# Bartosz_Nowakowski.net
KiCad netlist of a schematic drawn in EAGLE
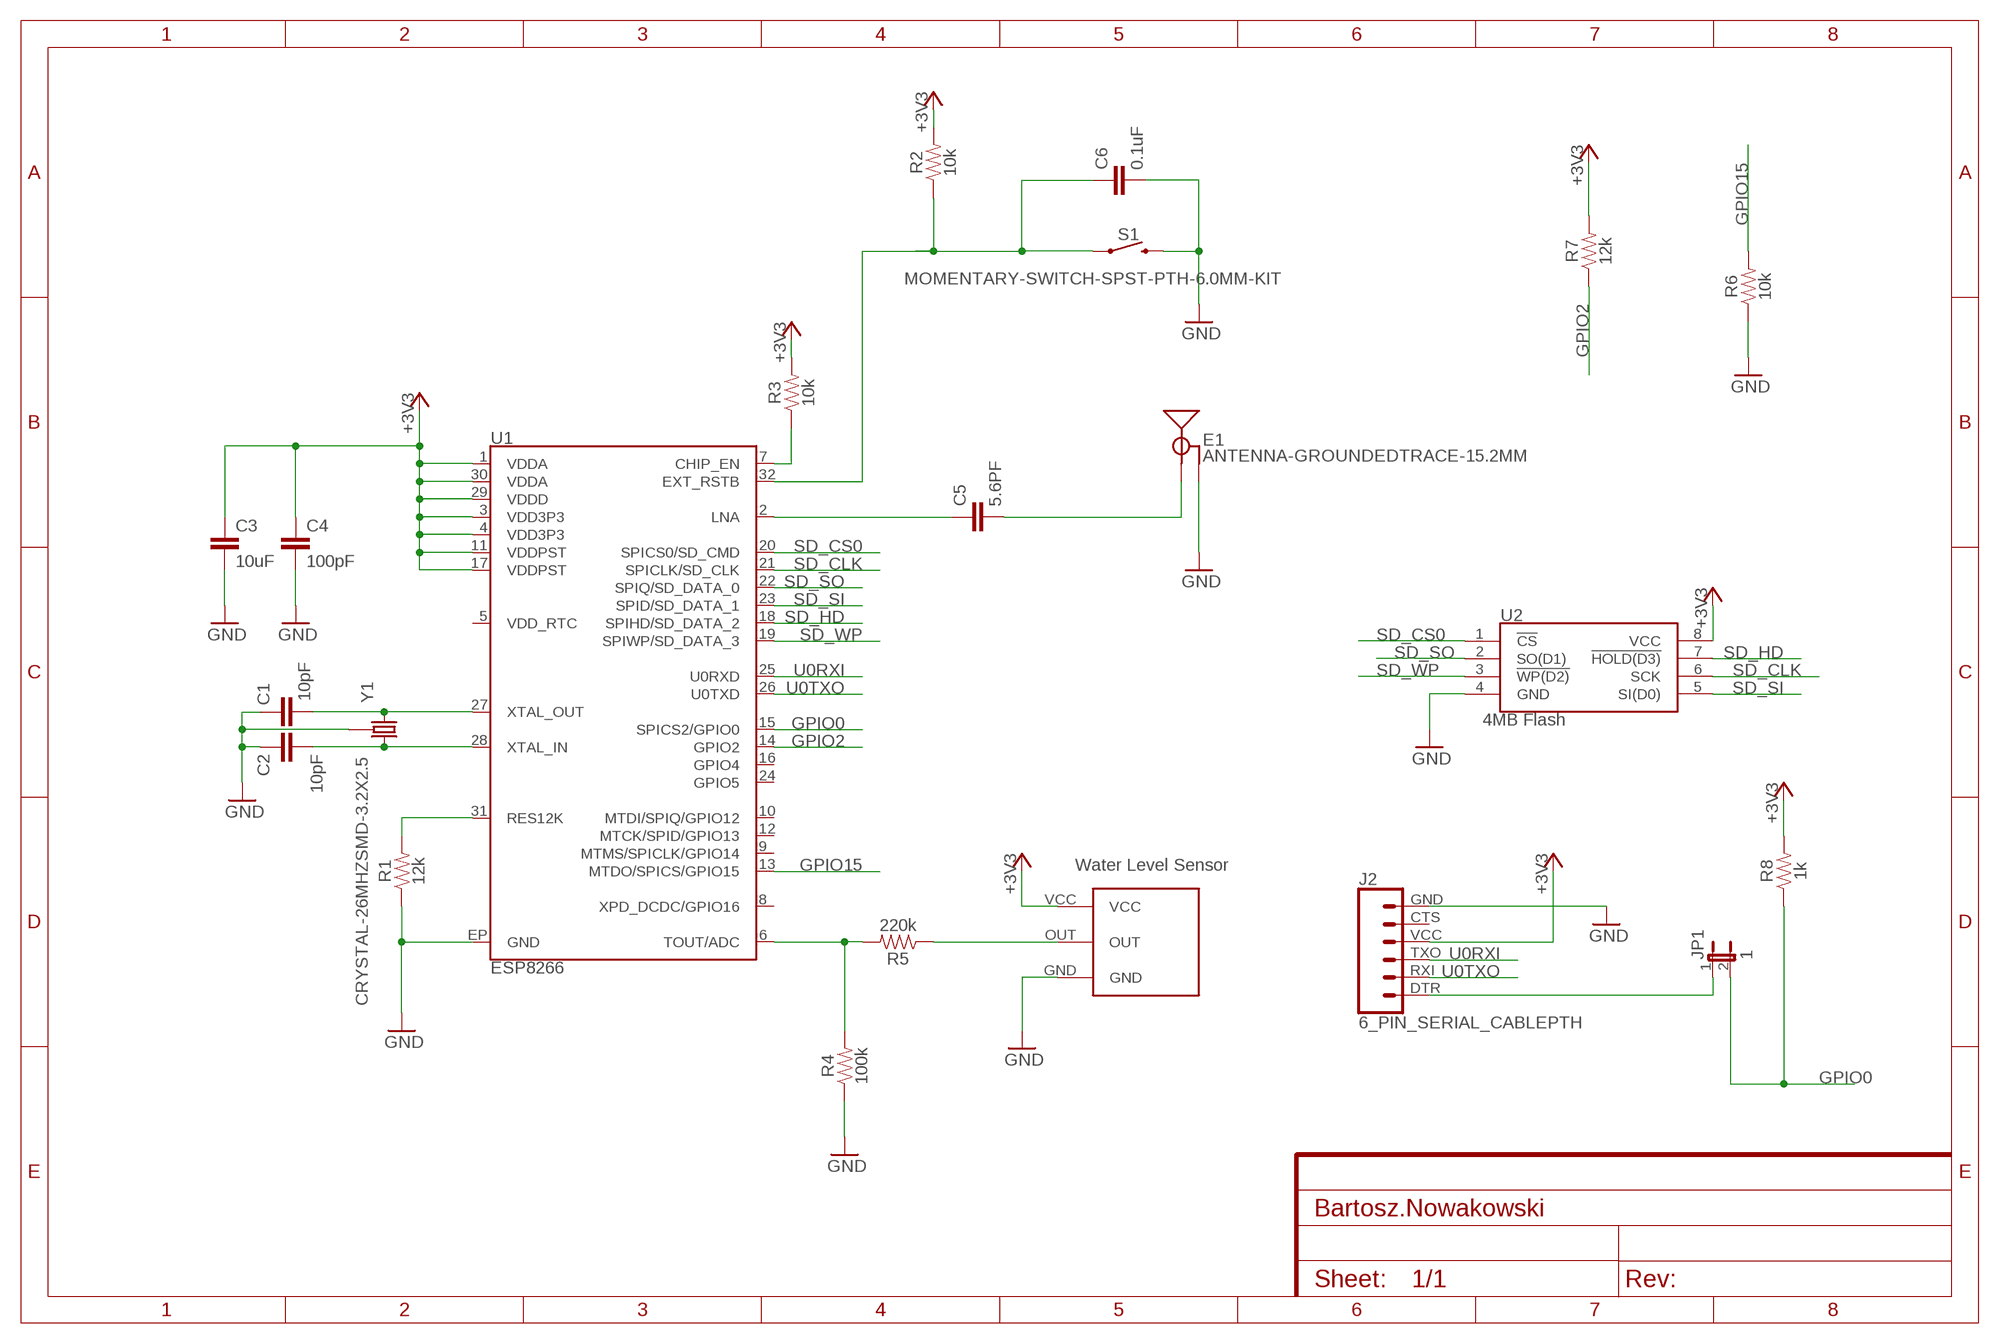
[diagram p0: schematic, sheet 1]

(export (version "E")
  (design (tool "Eeschema 10.0.6"))
  (components
    (comp (ref "C1")
      (value "10pF")
      (footprint "eagle-import:0603")
      (libsource (lib "eagle-import") (part "10PF-0603-50V-5%"))
    )
    (comp (ref "C2")
      (value "10pF")
      (footprint "eagle-import:0603")
      (libsource (lib "eagle-import") (part "10PF-0603-50V-5%"))
    )
    (comp (ref "C3")
      (value "10uF")
      (footprint "eagle-import:0805")
      (libsource (lib "eagle-import") (part "10UF-0805-10V-10%"))
    )
    (comp (ref "C4")
      (value "100pF")
      (footprint "eagle-import:0603")
      (libsource (lib "eagle-import") (part "100PF-0603-50V-5%"))
    )
    (comp (ref "C5")
      (value "5.6PF")
      (footprint "eagle-import:0603")
      (libsource (lib "eagle-import") (part "5.6PF-0603-50V-5%"))
    )
    (comp (ref "C6")
      (value "0.1uF")
      (footprint "eagle-import:0603")
      (libsource (lib "eagle-import") (part "0.1UF-0603-25V-5%"))
    )
    (comp (ref "E1")
      (value "ANTENNA-GROUNDEDTRACE-15.2MM")
      (footprint "eagle-import:TRACE_ANTENNA_2.4GHZ_15.2MM")
      (libsource (lib "eagle-import") (part "ANTENNA-GROUNDEDTRACE-15.2MM"))
    )
    (comp (ref "J2")
      (value "6_PIN_SERIAL_CABLEPTH")
      (footprint "eagle-import:FTDI_BASIC")
      (libsource (lib "eagle-import") (part "6_PIN_SERIAL_CABLEPTH"))
    )
    (comp (ref "JP1")
      (value "1")
      (footprint "eagle-import:JP1")
      (libsource (lib "eagle-import") (part "JP1E"))
    )
    (comp (ref "R1")
      (value "12k")
      (footprint "eagle-import:0603")
      (libsource (lib "eagle-import") (part "12KOHM-0603-1/10W-1%"))
    )
    (comp (ref "R2")
      (value "10k")
      (footprint "eagle-import:0603")
      (libsource (lib "eagle-import") (part "10KOHM-0603-1/10W-1%"))
    )
    (comp (ref "R3")
      (value "10k")
      (footprint "eagle-import:0603")
      (libsource (lib "eagle-import") (part "10KOHM-0603-1/10W-1%"))
    )
    (comp (ref "R4")
      (value "100k")
      (footprint "eagle-import:0603")
      (libsource (lib "eagle-import") (part "100KOHM-0603-1/10W-1%"))
    )
    (comp (ref "R5")
      (value "220k")
      (footprint "eagle-import:0603")
      (libsource (lib "eagle-import") (part "220KOHM-0603-1/10W-1%"))
    )
    (comp (ref "R6")
      (value "10k")
      (footprint "eagle-import:0603")
      (libsource (lib "eagle-import") (part "10KOHM-0603-1/10W-1%"))
    )
    (comp (ref "R7")
      (value "12k")
      (footprint "eagle-import:0603")
      (libsource (lib "eagle-import") (part "12KOHM-0603-1/10W-1%"))
    )
    (comp (ref "R8")
      (value "1k")
      (footprint "eagle-import:0603")
      (libsource (lib "eagle-import") (part "1KOHM-0603-1/10W-1%"))
    )
    (comp (ref "S1")
      (value "MOMENTARY-SWITCH-SPST-PTH-6.0MM-KIT")
      (footprint "eagle-import:TACTILE_SWITCH_PTH_6.0MM_KIT")
      (libsource (lib "eagle-import") (part "MOMENTARY-SWITCH-SPST-PTH-6.0MM-KIT"))
    )
    (comp (ref "U1")
      (value "ESP8266")
      (footprint "eagle-import:QFN32-5X5MM")
      (libsource (lib "eagle-import") (part "ESP8266"))
    )
    (comp (ref "U2")
      (value "4MB Flash")
      (footprint "eagle-import:SO08")
      (libsource (lib "eagle-import") (part "AT25SF041"))
    )
    (comp (ref "WATER1")
      (value "WATERLEVELSENORDEV")
      (footprint "eagle-import:WATERLEVELSENSORFT")
      (libsource (lib "eagle-import") (part "WATERLEVELSENORDEV"))
    )
    (comp (ref "Y1")
      (value "CRYSTAL-26MHZSMD-3.2X2.5")
      (footprint "eagle-import:CRYSTAL-SMD-3.2X2.5MM")
      (libsource (lib "eagle-import") (part "CRYSTAL-26MHZSMD-3.2X2.5"))
    )
  )
  (nets
    (net (code "1") (name "+3V3") (class "Default")
      (node (ref "C3") (pin "1") (pinfunction "1_1") (pintype "passive"))
      (node (ref "C4") (pin "1") (pinfunction "1_1") (pintype "passive"))
      (node (ref "J2") (pin "VCC") (pinfunction "4_VCC") (pintype "passive"))
      (node (ref "R2") (pin "2") (pinfunction "2_2") (pintype "passive"))
      (node (ref "R3") (pin "2") (pinfunction "2_2") (pintype "passive"))
      (node (ref "R7") (pin "2") (pinfunction "2_2") (pintype "passive"))
      (node (ref "R8") (pin "2") (pinfunction "2_2") (pintype "passive"))
      (node (ref "U1") (pin "1") (pinfunction "VDDA_1") (pintype "bidirectional"))
      (node (ref "U1") (pin "11") (pinfunction "VDDPST_11") (pintype "bidirectional"))
      (node (ref "U1") (pin "17") (pinfunction "VDDPST_17") (pintype "bidirectional"))
      (node (ref "U1") (pin "29") (pinfunction "VDDD_29") (pintype "bidirectional"))
      (node (ref "U1") (pin "3") (pinfunction "VDD3P3_3") (pintype "bidirectional"))
      (node (ref "U1") (pin "30") (pinfunction "VDDA_30") (pintype "bidirectional"))
      (node (ref "U1") (pin "4") (pinfunction "VDD3P3_4") (pintype "bidirectional"))
      (node (ref "U2") (pin "8") (pinfunction "VCC_8") (pintype "bidirectional"))
      (node (ref "WATER1") (pin "VCC") (pinfunction "VCC_VCC") (pintype "bidirectional"))
    )
    (net (code "2") (name "/GPIO0") (class "Default")
      (node (ref "JP1") (pin "2") (pinfunction "2_2") (pintype "passive"))
      (node (ref "R8") (pin "1") (pinfunction "1_1") (pintype "passive"))
      (node (ref "U1") (pin "15") (pinfunction "SPICS2/GPIO0_15") (pintype "bidirectional"))
    )
    (net (code "3") (name "/GPIO2") (class "Default")
      (node (ref "R7") (pin "1") (pinfunction "1_1") (pintype "passive"))
      (node (ref "U1") (pin "14") (pinfunction "GPIO2_14") (pintype "bidirectional"))
    )
    (net (code "4") (name "/GPIO15") (class "Default")
      (node (ref "R6") (pin "2") (pinfunction "2_2") (pintype "passive"))
      (node (ref "U1") (pin "13") (pinfunction "MTDO/SPICS/GPIO15_13") (pintype "bidirectional"))
    )
    (net (code "5") (name "/SD_CLK") (class "Default")
      (node (ref "U1") (pin "21") (pinfunction "SPICLK/SD_CLK_21") (pintype "bidirectional"))
      (node (ref "U2") (pin "6") (pinfunction "SCK_6") (pintype "bidirectional"))
    )
    (net (code "6") (name "/SD_CS0") (class "Default")
      (node (ref "U1") (pin "20") (pinfunction "SPICS0/SD_CMD_20") (pintype "bidirectional"))
      (node (ref "U2") (pin "1") (pinfunction "~{CS}_1") (pintype "bidirectional"))
    )
    (net (code "7") (name "/SD_HD") (class "Default")
      (node (ref "U1") (pin "18") (pinfunction "SPIHD/SD_DATA_2_18") (pintype "bidirectional"))
      (node (ref "U2") (pin "7") (pinfunction "~{HOLD(D3})_7") (pintype "bidirectional"))
    )
    (net (code "8") (name "/SD_SI") (class "Default")
      (node (ref "U1") (pin "23") (pinfunction "SPID/SD_DATA_1_23") (pintype "bidirectional"))
      (node (ref "U2") (pin "5") (pinfunction "SI(D0)_5") (pintype "bidirectional"))
    )
    (net (code "9") (name "/SD_SO") (class "Default")
      (node (ref "U1") (pin "22") (pinfunction "SPIQ/SD_DATA_0_22") (pintype "bidirectional"))
      (node (ref "U2") (pin "2") (pinfunction "SO(D1)_2") (pintype "bidirectional"))
    )
    (net (code "10") (name "/SD_WP") (class "Default")
      (node (ref "U1") (pin "19") (pinfunction "SPIWP/SD_DATA_3_19") (pintype "bidirectional"))
      (node (ref "U2") (pin "3") (pinfunction "~{WP(D2})_3") (pintype "bidirectional"))
    )
    (net (code "11") (name "/U0RXI") (class "Default")
      (node (ref "J2") (pin "TXO") (pinfunction "3_TXO") (pintype "passive"))
      (node (ref "U1") (pin "25") (pinfunction "U0RXD_25") (pintype "bidirectional"))
    )
    (net (code "12") (name "/U0TXO") (class "Default")
      (node (ref "J2") (pin "RXI") (pinfunction "2_RXI") (pintype "passive"))
      (node (ref "U1") (pin "26") (pinfunction "U0TXD_26") (pintype "bidirectional"))
    )
    (net (code "13") (name "GND") (class "Default")
      (node (ref "C1") (pin "1") (pinfunction "1_1") (pintype "passive"))
      (node (ref "C2") (pin "1") (pinfunction "1_1") (pintype "passive"))
      (node (ref "C3") (pin "2") (pinfunction "2_2") (pintype "passive"))
      (node (ref "C4") (pin "2") (pinfunction "2_2") (pintype "passive"))
      (node (ref "C6") (pin "2") (pinfunction "2_2") (pintype "passive"))
      (node (ref "E1") (pin "GND") (pinfunction "GND_GND") (pintype "bidirectional"))
      (node (ref "J2") (pin "GND") (pinfunction "6_GND") (pintype "passive"))
      (node (ref "R1") (pin "1") (pinfunction "1_1") (pintype "passive"))
      (node (ref "R4") (pin "1") (pinfunction "1_1") (pintype "passive"))
      (node (ref "R6") (pin "1") (pinfunction "1_1") (pintype "passive"))
      (node (ref "S1") (pin "3") (pinfunction "2_3") (pintype "passive"))
      (node (ref "U1") (pin "EP") (pinfunction "GND_EP") (pintype "bidirectional"))
      (node (ref "U2") (pin "4") (pinfunction "GND_4") (pintype "bidirectional"))
      (node (ref "WATER1") (pin "GND") (pinfunction "GND_GND") (pintype "bidirectional"))
      (node (ref "Y1") (pin "2") (pinfunction "3_2") (pintype "passive"))
      (node (ref "Y1") (pin "4") (pinfunction "3_4") (pintype "passive"))
    )
    (net (code "14") (name "Net-(E1-SIGNAL)") (class "Default")
      (node (ref "C5") (pin "2") (pinfunction "2_2") (pintype "passive"))
      (node (ref "E1") (pin "ANT") (pinfunction "SIGNAL_ANT") (pintype "bidirectional"))
    )
    (net (code "15") (name "Net-(J2-1)") (class "Default")
      (node (ref "J2") (pin "DTR") (pinfunction "1_DTR") (pintype "passive"))
      (node (ref "JP1") (pin "1") (pinfunction "1_1") (pintype "passive"))
    )
    (net (code "16") (name "Net-(R5-Pad1)") (class "Default")
      (node (ref "R5") (pin "1") (pinfunction "1_1") (pintype "passive"))
      (node (ref "WATER1") (pin "OUT") (pinfunction "OUT_OUT") (pintype "bidirectional"))
    )
    (net (code "17") (name "Net-(U1-CHIP_EN)") (class "Default")
      (node (ref "R3") (pin "1") (pinfunction "1_1") (pintype "passive"))
      (node (ref "U1") (pin "7") (pinfunction "CHIP_EN_7") (pintype "bidirectional"))
    )
    (net (code "18") (name "Net-(U1-EXT_RSTB)") (class "Default")
      (node (ref "C6") (pin "1") (pinfunction "1_1") (pintype "passive"))
      (node (ref "R2") (pin "1") (pinfunction "1_1") (pintype "passive"))
      (node (ref "S1") (pin "1") (pinfunction "1_1") (pintype "passive"))
      (node (ref "U1") (pin "32") (pinfunction "EXT_RSTB_32") (pintype "bidirectional"))
    )
    (net (code "19") (name "Net-(U1-LNA)") (class "Default")
      (node (ref "C5") (pin "1") (pinfunction "1_1") (pintype "passive"))
      (node (ref "U1") (pin "2") (pinfunction "LNA_2") (pintype "bidirectional"))
    )
    (net (code "20") (name "Net-(U1-RES12K)") (class "Default")
      (node (ref "R1") (pin "2") (pinfunction "2_2") (pintype "passive"))
      (node (ref "U1") (pin "31") (pinfunction "RES12K_31") (pintype "bidirectional"))
    )
    (net (code "21") (name "Net-(U1-TOUT{slash}ADC)") (class "Default")
      (node (ref "R4") (pin "2") (pinfunction "2_2") (pintype "passive"))
      (node (ref "R5") (pin "2") (pinfunction "2_2") (pintype "passive"))
      (node (ref "U1") (pin "6") (pinfunction "TOUT/ADC_6") (pintype "bidirectional"))
    )
    (net (code "22") (name "Net-(U1-XTAL_IN)") (class "Default")
      (node (ref "C2") (pin "2") (pinfunction "2_2") (pintype "passive"))
      (node (ref "U1") (pin "28") (pinfunction "XTAL_IN_28") (pintype "bidirectional"))
      (node (ref "Y1") (pin "3") (pinfunction "2_3") (pintype "passive"))
    )
    (net (code "23") (name "Net-(U1-XTAL_OUT)") (class "Default")
      (node (ref "C1") (pin "2") (pinfunction "2_2") (pintype "passive"))
      (node (ref "U1") (pin "27") (pinfunction "XTAL_OUT_27") (pintype "bidirectional"))
      (node (ref "Y1") (pin "1") (pinfunction "1_1") (pintype "passive"))
    )
    (net (code "24") (name "unconnected-(J2-5-PadCTS)") (class "Default")
      (node (ref "J2") (pin "CTS") (pinfunction "5_CTS") (pintype "passive"))
    )
    (net (code "25") (name "unconnected-(U1-GPIO4-Pad16)") (class "Default")
      (node (ref "U1") (pin "16") (pinfunction "GPIO4_16") (pintype "bidirectional"))
    )
    (net (code "26") (name "unconnected-(U1-GPIO5-Pad24)") (class "Default")
      (node (ref "U1") (pin "24") (pinfunction "GPIO5_24") (pintype "bidirectional"))
    )
    (net (code "27") (name "unconnected-(U1-MTCK{slash}SPID{slash}GPIO13-Pad12)") (class "Default")
      (node (ref "U1") (pin "12") (pinfunction "MTCK/SPID/GPIO13_12") (pintype "bidirectional"))
    )
    (net (code "28") (name "unconnected-(U1-MTDI{slash}SPIQ{slash}GPIO12-Pad10)") (class "Default")
      (node (ref "U1") (pin "10") (pinfunction "MTDI/SPIQ/GPIO12_10") (pintype "bidirectional"))
    )
    (net (code "29") (name "unconnected-(U1-MTMS{slash}SPICLK{slash}GPIO14-Pad9)") (class "Default")
      (node (ref "U1") (pin "9") (pinfunction "MTMS/SPICLK/GPIO14_9") (pintype "bidirectional"))
    )
    (net (code "30") (name "unconnected-(U1-VDD_RTC-Pad5)") (class "Default")
      (node (ref "U1") (pin "5") (pinfunction "VDD_RTC_5") (pintype "bidirectional"))
    )
    (net (code "31") (name "unconnected-(U1-XPD_DCDC{slash}GPIO16-Pad8)") (class "Default")
      (node (ref "U1") (pin "8") (pinfunction "XPD_DCDC/GPIO16_8") (pintype "bidirectional"))
    )
  )
)
